# FPGA.net
KiCad netlist of a schematic drawn in Altium Designer
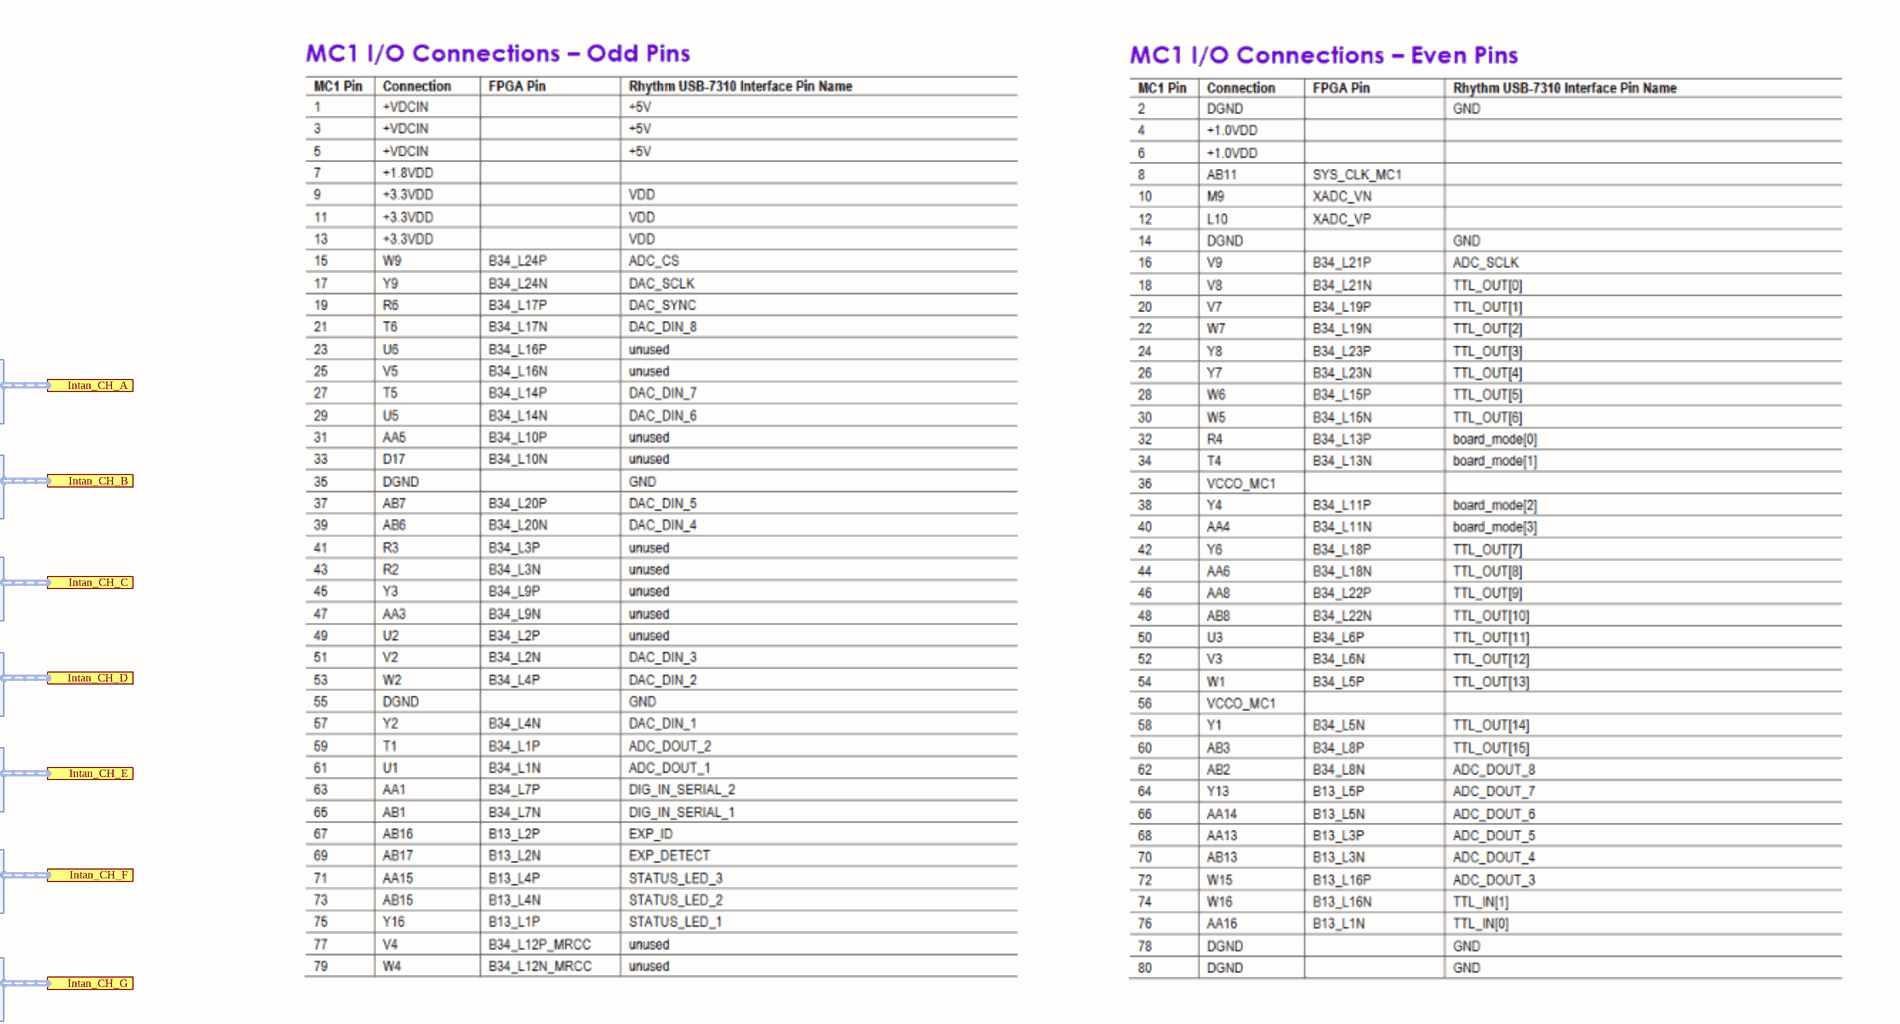
[diagram p0: FPGA.SchDoc, top right]
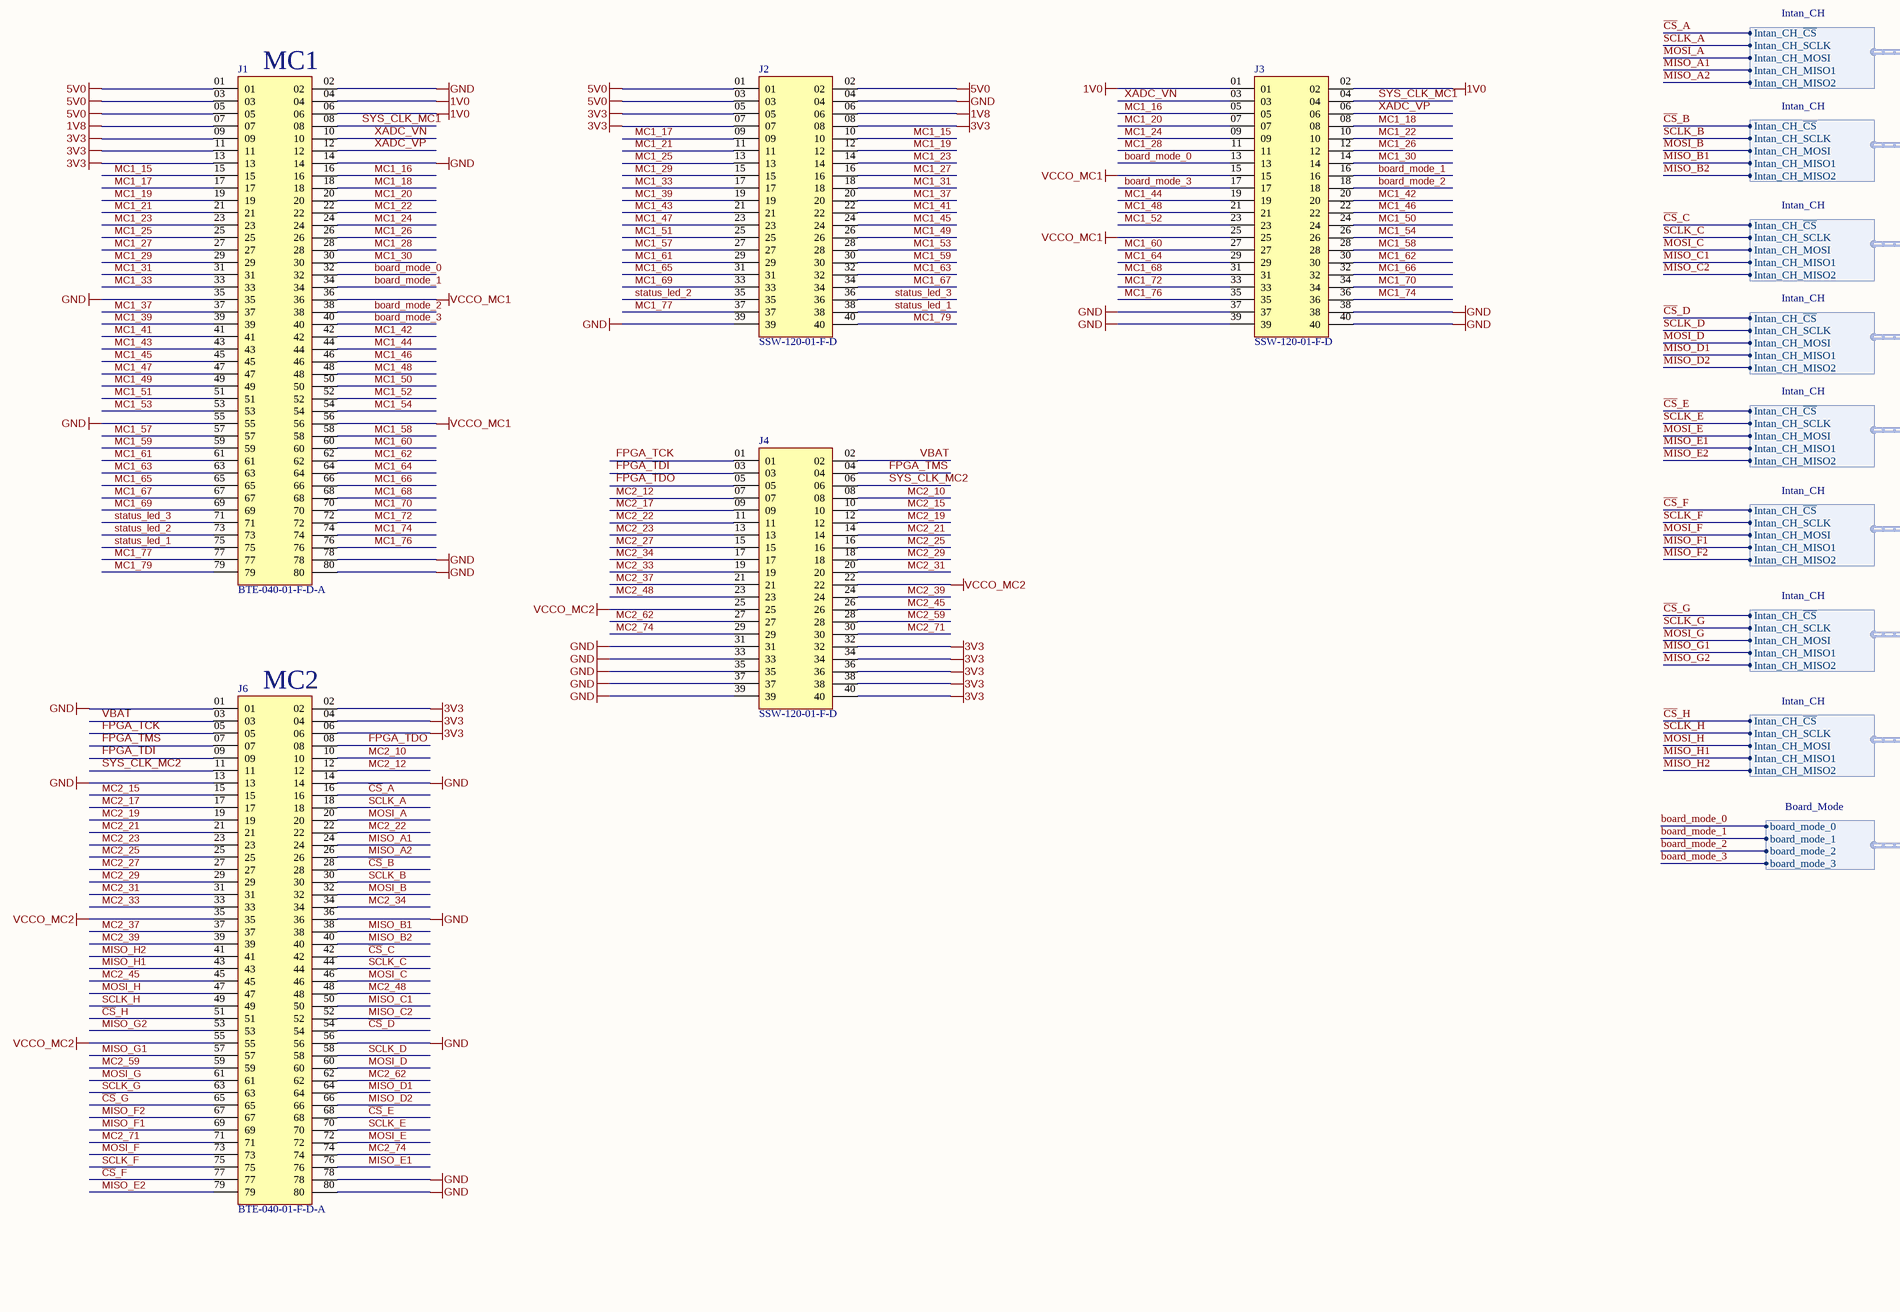
[diagram p1: FPGA.SchDoc, bottom left]
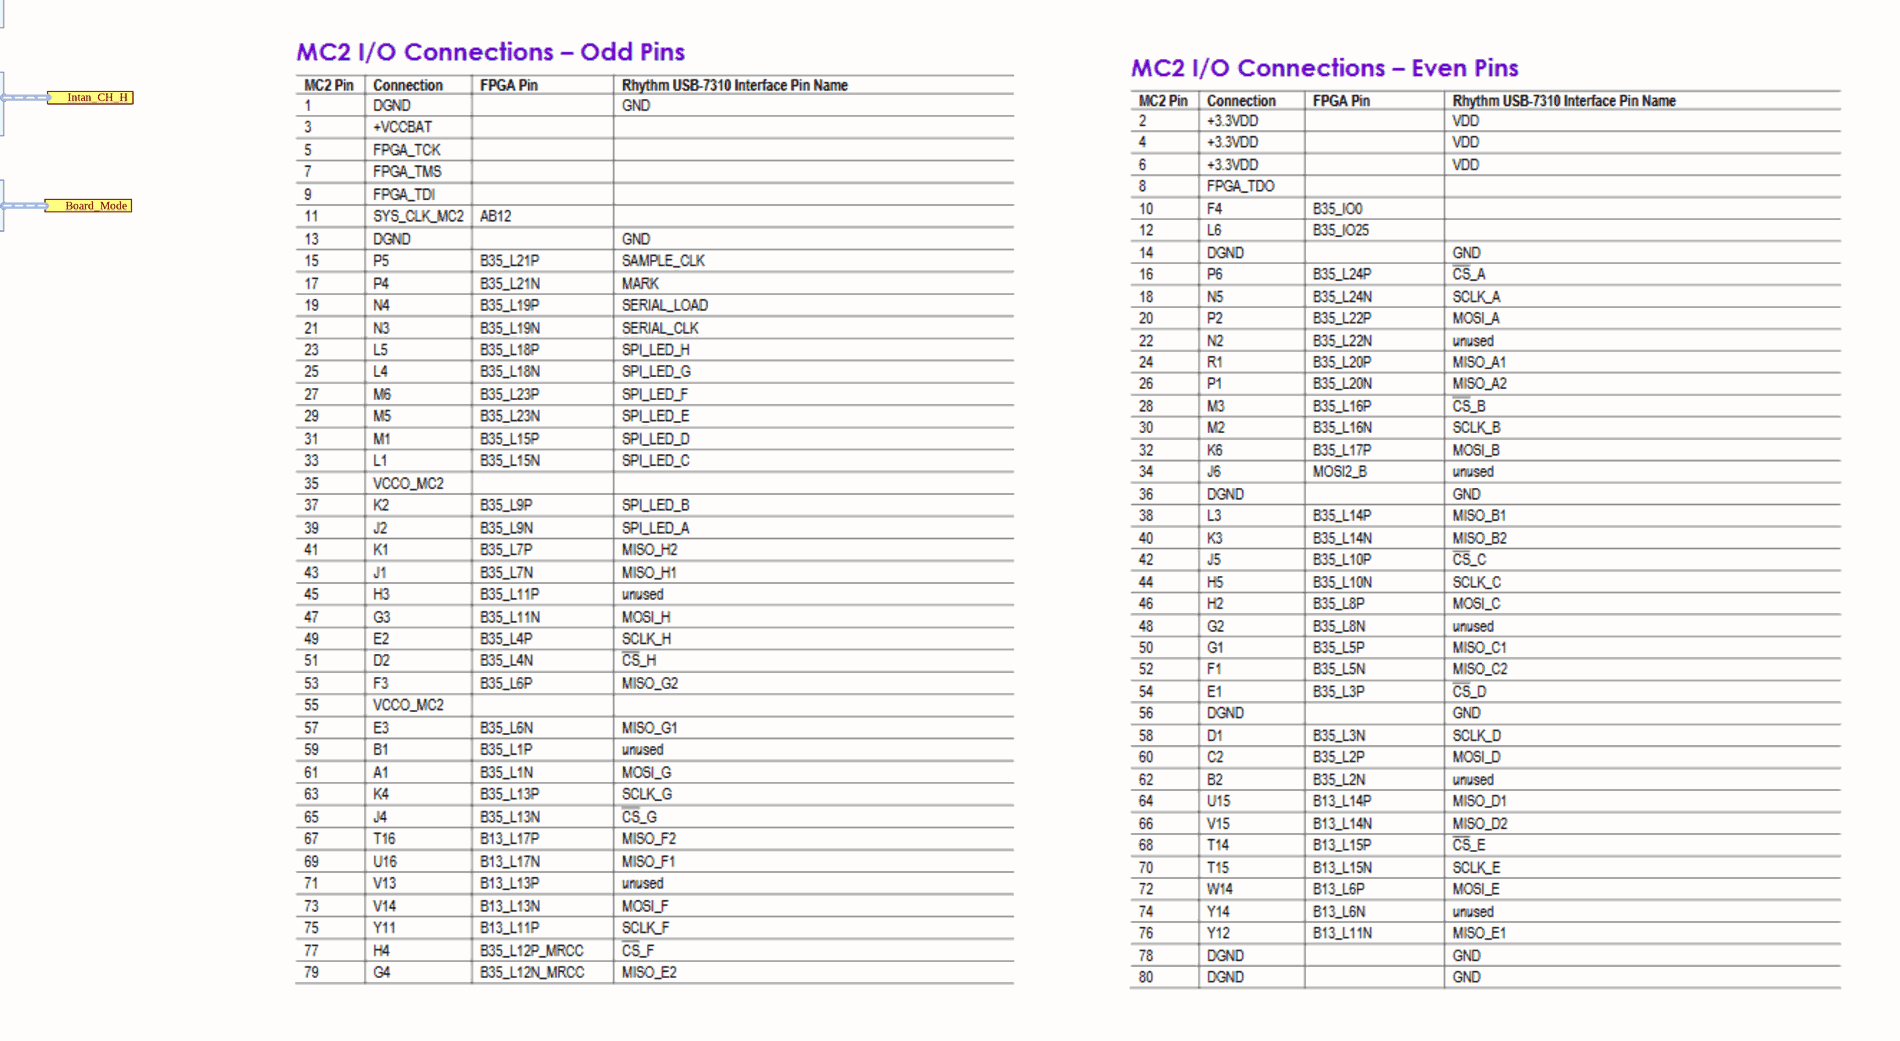
[diagram p2: FPGA.SchDoc, bottom right]

(export (version "E")
  (design (tool "Eeschema 10.0.6"))
  (components
    (comp (ref "J1")
      (value "BTE-040-01-F-D-A")
      (footprint "SAMTEC_BTE-040-01-F-D-A")
      (description "80 Position Connector Header, Outer Shroud Contacts Surface Mount Gold")
      (fields (field (name "MF") "Samtec"))
      (libsource (lib "UHDEMG") (part "CON_FPGA_SMD"))
    )
    (comp (ref "J2")
      (value "SSW-120-01-F-D")
      (footprint "SAMTEC_SSW-120-01-F-D")
      (description "40 Position Receptacle Connector 0.100\" (2.54mm) Through Hole Gold")
      (fields (field (name "MF") "Samtec"))
      (libsource (lib "UHDEMG") (part "CON_HEADF_2X20"))
    )
    (comp (ref "J3")
      (value "SSW-120-01-F-D")
      (footprint "SAMTEC_SSW-120-01-F-D")
      (description "40 Position Receptacle Connector 0.100\" (2.54mm) Through Hole Gold")
      (fields (field (name "MF") "Samtec"))
      (libsource (lib "UHDEMG") (part "CON_HEADF_2X20"))
    )
    (comp (ref "J4")
      (value "SSW-120-01-F-D")
      (footprint "SAMTEC_SSW-120-01-F-D")
      (description "40 Position Receptacle Connector 0.100\" (2.54mm) Through Hole Gold")
      (fields (field (name "MF") "Samtec"))
      (libsource (lib "UHDEMG") (part "CON_HEADF_2X20"))
    )
    (comp (ref "J6")
      (value "BTE-040-01-F-D-A")
      (footprint "SAMTEC_BTE-040-01-F-D-A")
      (description "80 Position Connector Header, Outer Shroud Contacts Surface Mount Gold")
      (fields (field (name "MF") "Samtec"))
      (libsource (lib "UHDEMG") (part "CON_FPGA_SMD"))
    )
  )
  (nets
    (net (code "3") (name "/FPGA_TCK") (class "Default")
      (node (ref "J4") (pin "01") (pinfunction "01_01") (pintype "passive"))
      (node (ref "J6") (pin "05") (pinfunction "05_05") (pintype "passive"))
    )
    (net (code "4") (name "/FPGA_TDI") (class "Default")
      (node (ref "J4") (pin "03") (pinfunction "03_03") (pintype "passive"))
      (node (ref "J6") (pin "09") (pinfunction "09_09") (pintype "passive"))
    )
    (net (code "5") (name "/FPGA_TDO") (class "Default")
      (node (ref "J4") (pin "05") (pinfunction "05_05") (pintype "passive"))
      (node (ref "J6") (pin "08") (pinfunction "08_08") (pintype "passive"))
    )
    (net (code "6") (name "/FPGA_TMS") (class "Default")
      (node (ref "J4") (pin "04") (pinfunction "04_04") (pintype "passive"))
      (node (ref "J6") (pin "07") (pinfunction "07_07") (pintype "passive"))
    )
    (net (code "7") (name "/MC1_15") (class "Default")
      (node (ref "J1") (pin "15") (pinfunction "15_15") (pintype "passive"))
      (node (ref "J2") (pin "10") (pinfunction "10_10") (pintype "passive"))
    )
    (net (code "8") (name "/MC1_16") (class "Default")
      (node (ref "J1") (pin "16") (pinfunction "16_16") (pintype "passive"))
      (node (ref "J3") (pin "05") (pinfunction "05_05") (pintype "passive"))
    )
    (net (code "9") (name "/MC1_17") (class "Default")
      (node (ref "J1") (pin "17") (pinfunction "17_17") (pintype "passive"))
      (node (ref "J2") (pin "09") (pinfunction "09_09") (pintype "passive"))
    )
    (net (code "10") (name "/MC1_18") (class "Default")
      (node (ref "J1") (pin "18") (pinfunction "18_18") (pintype "passive"))
      (node (ref "J3") (pin "08") (pinfunction "08_08") (pintype "passive"))
    )
    (net (code "11") (name "/MC1_19") (class "Default")
      (node (ref "J1") (pin "19") (pinfunction "19_19") (pintype "passive"))
      (node (ref "J2") (pin "12") (pinfunction "12_12") (pintype "passive"))
    )
    (net (code "12") (name "/MC1_20") (class "Default")
      (node (ref "J1") (pin "20") (pinfunction "20_20") (pintype "passive"))
      (node (ref "J3") (pin "07") (pinfunction "07_07") (pintype "passive"))
    )
    (net (code "13") (name "/MC1_21") (class "Default")
      (node (ref "J1") (pin "21") (pinfunction "21_21") (pintype "passive"))
      (node (ref "J2") (pin "11") (pinfunction "11_11") (pintype "passive"))
    )
    (net (code "14") (name "/MC1_22") (class "Default")
      (node (ref "J1") (pin "22") (pinfunction "22_22") (pintype "passive"))
      (node (ref "J3") (pin "10") (pinfunction "10_10") (pintype "passive"))
    )
    (net (code "15") (name "/MC1_23") (class "Default")
      (node (ref "J1") (pin "23") (pinfunction "23_23") (pintype "passive"))
      (node (ref "J2") (pin "14") (pinfunction "14_14") (pintype "passive"))
    )
    (net (code "16") (name "/MC1_24") (class "Default")
      (node (ref "J1") (pin "24") (pinfunction "24_24") (pintype "passive"))
      (node (ref "J3") (pin "09") (pinfunction "09_09") (pintype "passive"))
    )
    (net (code "17") (name "/MC1_25") (class "Default")
      (node (ref "J1") (pin "25") (pinfunction "25_25") (pintype "passive"))
      (node (ref "J2") (pin "13") (pinfunction "13_13") (pintype "passive"))
    )
    (net (code "18") (name "/MC1_26") (class "Default")
      (node (ref "J1") (pin "26") (pinfunction "26_26") (pintype "passive"))
      (node (ref "J3") (pin "12") (pinfunction "12_12") (pintype "passive"))
    )
    (net (code "19") (name "/MC1_27") (class "Default")
      (node (ref "J1") (pin "27") (pinfunction "27_27") (pintype "passive"))
      (node (ref "J2") (pin "16") (pinfunction "16_16") (pintype "passive"))
    )
    (net (code "20") (name "/MC1_28") (class "Default")
      (node (ref "J1") (pin "28") (pinfunction "28_28") (pintype "passive"))
      (node (ref "J3") (pin "11") (pinfunction "11_11") (pintype "passive"))
    )
    (net (code "21") (name "/MC1_29") (class "Default")
      (node (ref "J1") (pin "29") (pinfunction "29_29") (pintype "passive"))
      (node (ref "J2") (pin "15") (pinfunction "15_15") (pintype "passive"))
    )
    (net (code "22") (name "/MC1_30") (class "Default")
      (node (ref "J1") (pin "30") (pinfunction "30_30") (pintype "passive"))
      (node (ref "J3") (pin "14") (pinfunction "14_14") (pintype "passive"))
    )
    (net (code "23") (name "/MC1_31") (class "Default")
      (node (ref "J1") (pin "31") (pinfunction "31_31") (pintype "passive"))
      (node (ref "J2") (pin "18") (pinfunction "18_18") (pintype "passive"))
    )
    (net (code "24") (name "/MC1_33") (class "Default")
      (node (ref "J1") (pin "33") (pinfunction "33_33") (pintype "passive"))
      (node (ref "J2") (pin "17") (pinfunction "17_17") (pintype "passive"))
    )
    (net (code "25") (name "/MC1_37") (class "Default")
      (node (ref "J1") (pin "37") (pinfunction "37_37") (pintype "passive"))
      (node (ref "J2") (pin "20") (pinfunction "20_20") (pintype "passive"))
    )
    (net (code "26") (name "/MC1_39") (class "Default")
      (node (ref "J1") (pin "39") (pinfunction "39_39") (pintype "passive"))
      (node (ref "J2") (pin "19") (pinfunction "19_19") (pintype "passive"))
    )
    (net (code "27") (name "/MC1_41") (class "Default")
      (node (ref "J1") (pin "41") (pinfunction "41_41") (pintype "passive"))
      (node (ref "J2") (pin "22") (pinfunction "22_22") (pintype "passive"))
    )
    (net (code "28") (name "/MC1_42") (class "Default")
      (node (ref "J1") (pin "42") (pinfunction "42_42") (pintype "passive"))
      (node (ref "J3") (pin "20") (pinfunction "20_20") (pintype "passive"))
    )
    (net (code "29") (name "/MC1_43") (class "Default")
      (node (ref "J1") (pin "43") (pinfunction "43_43") (pintype "passive"))
      (node (ref "J2") (pin "21") (pinfunction "21_21") (pintype "passive"))
    )
    (net (code "30") (name "/MC1_44") (class "Default")
      (node (ref "J1") (pin "44") (pinfunction "44_44") (pintype "passive"))
      (node (ref "J3") (pin "19") (pinfunction "19_19") (pintype "passive"))
    )
    (net (code "31") (name "/MC1_45") (class "Default")
      (node (ref "J1") (pin "45") (pinfunction "45_45") (pintype "passive"))
      (node (ref "J2") (pin "24") (pinfunction "24_24") (pintype "passive"))
    )
    (net (code "32") (name "/MC1_46") (class "Default")
      (node (ref "J1") (pin "46") (pinfunction "46_46") (pintype "passive"))
      (node (ref "J3") (pin "22") (pinfunction "22_22") (pintype "passive"))
    )
    (net (code "33") (name "/MC1_47") (class "Default")
      (node (ref "J1") (pin "47") (pinfunction "47_47") (pintype "passive"))
      (node (ref "J2") (pin "23") (pinfunction "23_23") (pintype "passive"))
    )
    (net (code "34") (name "/MC1_48") (class "Default")
      (node (ref "J1") (pin "48") (pinfunction "48_48") (pintype "passive"))
      (node (ref "J3") (pin "21") (pinfunction "21_21") (pintype "passive"))
    )
    (net (code "35") (name "/MC1_49") (class "Default")
      (node (ref "J1") (pin "49") (pinfunction "49_49") (pintype "passive"))
      (node (ref "J2") (pin "26") (pinfunction "26_26") (pintype "passive"))
    )
    (net (code "36") (name "/MC1_50") (class "Default")
      (node (ref "J1") (pin "50") (pinfunction "50_50") (pintype "passive"))
      (node (ref "J3") (pin "24") (pinfunction "24_24") (pintype "passive"))
    )
    (net (code "37") (name "/MC1_51") (class "Default")
      (node (ref "J1") (pin "51") (pinfunction "51_51") (pintype "passive"))
      (node (ref "J2") (pin "25") (pinfunction "25_25") (pintype "passive"))
    )
    (net (code "38") (name "/MC1_52") (class "Default")
      (node (ref "J1") (pin "52") (pinfunction "52_52") (pintype "passive"))
      (node (ref "J3") (pin "23") (pinfunction "23_23") (pintype "passive"))
    )
    (net (code "39") (name "/MC1_53") (class "Default")
      (node (ref "J1") (pin "53") (pinfunction "53_53") (pintype "passive"))
      (node (ref "J2") (pin "28") (pinfunction "28_28") (pintype "passive"))
    )
    (net (code "40") (name "/MC1_54") (class "Default")
      (node (ref "J1") (pin "54") (pinfunction "54_54") (pintype "passive"))
      (node (ref "J3") (pin "26") (pinfunction "26_26") (pintype "passive"))
    )
    (net (code "41") (name "/MC1_57") (class "Default")
      (node (ref "J1") (pin "57") (pinfunction "57_57") (pintype "passive"))
      (node (ref "J2") (pin "27") (pinfunction "27_27") (pintype "passive"))
    )
    (net (code "42") (name "/MC1_58") (class "Default")
      (node (ref "J1") (pin "58") (pinfunction "58_58") (pintype "passive"))
      (node (ref "J3") (pin "28") (pinfunction "28_28") (pintype "passive"))
    )
    (net (code "43") (name "/MC1_59") (class "Default")
      (node (ref "J1") (pin "59") (pinfunction "59_59") (pintype "passive"))
      (node (ref "J2") (pin "30") (pinfunction "30_30") (pintype "passive"))
    )
    (net (code "44") (name "/MC1_60") (class "Default")
      (node (ref "J1") (pin "60") (pinfunction "60_60") (pintype "passive"))
      (node (ref "J3") (pin "27") (pinfunction "27_27") (pintype "passive"))
    )
    (net (code "45") (name "/MC1_61") (class "Default")
      (node (ref "J1") (pin "61") (pinfunction "61_61") (pintype "passive"))
      (node (ref "J2") (pin "29") (pinfunction "29_29") (pintype "passive"))
    )
    (net (code "46") (name "/MC1_62") (class "Default")
      (node (ref "J1") (pin "62") (pinfunction "62_62") (pintype "passive"))
      (node (ref "J3") (pin "30") (pinfunction "30_30") (pintype "passive"))
    )
    (net (code "47") (name "/MC1_63") (class "Default")
      (node (ref "J1") (pin "63") (pinfunction "63_63") (pintype "passive"))
      (node (ref "J2") (pin "32") (pinfunction "32_32") (pintype "passive"))
    )
    (net (code "48") (name "/MC1_64") (class "Default")
      (node (ref "J1") (pin "64") (pinfunction "64_64") (pintype "passive"))
      (node (ref "J3") (pin "29") (pinfunction "29_29") (pintype "passive"))
    )
    (net (code "49") (name "/MC1_65") (class "Default")
      (node (ref "J1") (pin "65") (pinfunction "65_65") (pintype "passive"))
      (node (ref "J2") (pin "31") (pinfunction "31_31") (pintype "passive"))
    )
    (net (code "50") (name "/MC1_66") (class "Default")
      (node (ref "J1") (pin "66") (pinfunction "66_66") (pintype "passive"))
      (node (ref "J3") (pin "32") (pinfunction "32_32") (pintype "passive"))
    )
    (net (code "51") (name "/MC1_67") (class "Default")
      (node (ref "J1") (pin "67") (pinfunction "67_67") (pintype "passive"))
      (node (ref "J2") (pin "34") (pinfunction "34_34") (pintype "passive"))
    )
    (net (code "52") (name "/MC1_68") (class "Default")
      (node (ref "J1") (pin "68") (pinfunction "68_68") (pintype "passive"))
      (node (ref "J3") (pin "31") (pinfunction "31_31") (pintype "passive"))
    )
    (net (code "53") (name "/MC1_69") (class "Default")
      (node (ref "J1") (pin "69") (pinfunction "69_69") (pintype "passive"))
      (node (ref "J2") (pin "33") (pinfunction "33_33") (pintype "passive"))
    )
    (net (code "54") (name "/MC1_70") (class "Default")
      (node (ref "J1") (pin "70") (pinfunction "70_70") (pintype "passive"))
      (node (ref "J3") (pin "34") (pinfunction "34_34") (pintype "passive"))
    )
    (net (code "55") (name "/MC1_72") (class "Default")
      (node (ref "J1") (pin "72") (pinfunction "72_72") (pintype "passive"))
      (node (ref "J3") (pin "33") (pinfunction "33_33") (pintype "passive"))
    )
    (net (code "56") (name "/MC1_74") (class "Default")
      (node (ref "J1") (pin "74") (pinfunction "74_74") (pintype "passive"))
      (node (ref "J3") (pin "36") (pinfunction "36_36") (pintype "passive"))
    )
    (net (code "57") (name "/MC1_76") (class "Default")
      (node (ref "J1") (pin "76") (pinfunction "76_76") (pintype "passive"))
      (node (ref "J3") (pin "35") (pinfunction "35_35") (pintype "passive"))
    )
    (net (code "58") (name "/MC1_77") (class "Default")
      (node (ref "J1") (pin "77") (pinfunction "77_77") (pintype "passive"))
      (node (ref "J2") (pin "37") (pinfunction "37_37") (pintype "passive"))
    )
    (net (code "59") (name "/MC1_79") (class "Default")
      (node (ref "J1") (pin "79") (pinfunction "79_79") (pintype "passive"))
      (node (ref "J2") (pin "40") (pinfunction "40_40") (pintype "passive"))
    )
    (net (code "60") (name "/MC2_10") (class "Default")
      (node (ref "J4") (pin "08") (pinfunction "08_08") (pintype "passive"))
      (node (ref "J6") (pin "10") (pinfunction "10_10") (pintype "passive"))
    )
    (net (code "61") (name "/MC2_12") (class "Default")
      (node (ref "J4") (pin "07") (pinfunction "07_07") (pintype "passive"))
      (node (ref "J6") (pin "12") (pinfunction "12_12") (pintype "passive"))
    )
    (net (code "62") (name "/MC2_15") (class "Default")
      (node (ref "J4") (pin "10") (pinfunction "10_10") (pintype "passive"))
      (node (ref "J6") (pin "15") (pinfunction "15_15") (pintype "passive"))
    )
    (net (code "63") (name "/MC2_17") (class "Default")
      (node (ref "J4") (pin "09") (pinfunction "09_09") (pintype "passive"))
      (node (ref "J6") (pin "17") (pinfunction "17_17") (pintype "passive"))
    )
    (net (code "64") (name "/MC2_19") (class "Default")
      (node (ref "J4") (pin "12") (pinfunction "12_12") (pintype "passive"))
      (node (ref "J6") (pin "19") (pinfunction "19_19") (pintype "passive"))
    )
    (net (code "65") (name "/MC2_21") (class "Default")
      (node (ref "J4") (pin "14") (pinfunction "14_14") (pintype "passive"))
      (node (ref "J6") (pin "21") (pinfunction "21_21") (pintype "passive"))
    )
    (net (code "66") (name "/MC2_22") (class "Default")
      (node (ref "J4") (pin "11") (pinfunction "11_11") (pintype "passive"))
      (node (ref "J6") (pin "22") (pinfunction "22_22") (pintype "passive"))
    )
    (net (code "67") (name "/MC2_23") (class "Default")
      (node (ref "J4") (pin "13") (pinfunction "13_13") (pintype "passive"))
      (node (ref "J6") (pin "23") (pinfunction "23_23") (pintype "passive"))
    )
    (net (code "68") (name "/MC2_25") (class "Default")
      (node (ref "J4") (pin "16") (pinfunction "16_16") (pintype "passive"))
      (node (ref "J6") (pin "25") (pinfunction "25_25") (pintype "passive"))
    )
    (net (code "69") (name "/MC2_27") (class "Default")
      (node (ref "J4") (pin "15") (pinfunction "15_15") (pintype "passive"))
      (node (ref "J6") (pin "27") (pinfunction "27_27") (pintype "passive"))
    )
    (net (code "70") (name "/MC2_29") (class "Default")
      (node (ref "J4") (pin "18") (pinfunction "18_18") (pintype "passive"))
      (node (ref "J6") (pin "29") (pinfunction "29_29") (pintype "passive"))
    )
    (net (code "71") (name "/MC2_31") (class "Default")
      (node (ref "J4") (pin "20") (pinfunction "20_20") (pintype "passive"))
      (node (ref "J6") (pin "31") (pinfunction "31_31") (pintype "passive"))
    )
    (net (code "72") (name "/MC2_33") (class "Default")
      (node (ref "J4") (pin "19") (pinfunction "19_19") (pintype "passive"))
      (node (ref "J6") (pin "33") (pinfunction "33_33") (pintype "passive"))
    )
    (net (code "73") (name "/MC2_34") (class "Default")
      (node (ref "J4") (pin "17") (pinfunction "17_17") (pintype "passive"))
      (node (ref "J6") (pin "34") (pinfunction "34_34") (pintype "passive"))
    )
    (net (code "74") (name "/MC2_37") (class "Default")
      (node (ref "J4") (pin "21") (pinfunction "21_21") (pintype "passive"))
      (node (ref "J6") (pin "37") (pinfunction "37_37") (pintype "passive"))
    )
    (net (code "75") (name "/MC2_39") (class "Default")
      (node (ref "J4") (pin "24") (pinfunction "24_24") (pintype "passive"))
      (node (ref "J6") (pin "39") (pinfunction "39_39") (pintype "passive"))
    )
    (net (code "76") (name "/MC2_45") (class "Default")
      (node (ref "J4") (pin "26") (pinfunction "26_26") (pintype "passive"))
      (node (ref "J6") (pin "45") (pinfunction "45_45") (pintype "passive"))
    )
    (net (code "77") (name "/MC2_48") (class "Default")
      (node (ref "J4") (pin "23") (pinfunction "23_23") (pintype "passive"))
      (node (ref "J6") (pin "48") (pinfunction "48_48") (pintype "passive"))
    )
    (net (code "78") (name "/MC2_59") (class "Default")
      (node (ref "J4") (pin "28") (pinfunction "28_28") (pintype "passive"))
      (node (ref "J6") (pin "59") (pinfunction "59_59") (pintype "passive"))
    )
    (net (code "79") (name "/MC2_62") (class "Default")
      (node (ref "J4") (pin "27") (pinfunction "27_27") (pintype "passive"))
      (node (ref "J6") (pin "62") (pinfunction "62_62") (pintype "passive"))
    )
    (net (code "80") (name "/MC2_71") (class "Default")
      (node (ref "J4") (pin "30") (pinfunction "30_30") (pintype "passive"))
      (node (ref "J6") (pin "71") (pinfunction "71_71") (pintype "passive"))
    )
    (net (code "81") (name "/MC2_74") (class "Default")
      (node (ref "J4") (pin "29") (pinfunction "29_29") (pintype "passive"))
      (node (ref "J6") (pin "74") (pinfunction "74_74") (pintype "passive"))
    )
    (net (code "82") (name "/MISO_A1") (class "Default")
      (node (ref "J6") (pin "24") (pinfunction "24_24") (pintype "passive"))
    )
    (net (code "83") (name "/MISO_A2") (class "Default")
      (node (ref "J6") (pin "26") (pinfunction "26_26") (pintype "passive"))
    )
    (net (code "84") (name "/MISO_B1") (class "Default")
      (node (ref "J6") (pin "38") (pinfunction "38_38") (pintype "passive"))
    )
    (net (code "85") (name "/MISO_B2") (class "Default")
      (node (ref "J6") (pin "40") (pinfunction "40_40") (pintype "passive"))
    )
    (net (code "86") (name "/MISO_C1") (class "Default")
      (node (ref "J6") (pin "50") (pinfunction "50_50") (pintype "passive"))
    )
    (net (code "87") (name "/MISO_C2") (class "Default")
      (node (ref "J6") (pin "52") (pinfunction "52_52") (pintype "passive"))
    )
    (net (code "88") (name "/MISO_D1") (class "Default")
      (node (ref "J6") (pin "64") (pinfunction "64_64") (pintype "passive"))
    )
    (net (code "89") (name "/MISO_D2") (class "Default")
      (node (ref "J6") (pin "66") (pinfunction "66_66") (pintype "passive"))
    )
    (net (code "90") (name "/MISO_E1") (class "Default")
      (node (ref "J6") (pin "76") (pinfunction "76_76") (pintype "passive"))
    )
    (net (code "91") (name "/MISO_E2") (class "Default")
      (node (ref "J6") (pin "79") (pinfunction "79_79") (pintype "passive"))
    )
    (net (code "92") (name "/MISO_F1") (class "Default")
      (node (ref "J6") (pin "69") (pinfunction "69_69") (pintype "passive"))
    )
    (net (code "93") (name "/MISO_F2") (class "Default")
      (node (ref "J6") (pin "67") (pinfunction "67_67") (pintype "passive"))
    )
    (net (code "94") (name "/MISO_G1") (class "Default")
      (node (ref "J6") (pin "57") (pinfunction "57_57") (pintype "passive"))
    )
    (net (code "95") (name "/MISO_G2") (class "Default")
      (node (ref "J6") (pin "53") (pinfunction "53_53") (pintype "passive"))
    )
    (net (code "96") (name "/MISO_H1") (class "Default")
      (node (ref "J6") (pin "43") (pinfunction "43_43") (pintype "passive"))
    )
    (net (code "97") (name "/MISO_H2") (class "Default")
      (node (ref "J6") (pin "41") (pinfunction "41_41") (pintype "passive"))
    )
    (net (code "98") (name "/MOSI_A") (class "Default")
      (node (ref "J6") (pin "20") (pinfunction "20_20") (pintype "passive"))
    )
    (net (code "99") (name "/MOSI_B") (class "Default")
      (node (ref "J6") (pin "32") (pinfunction "32_32") (pintype "passive"))
    )
    (net (code "100") (name "/MOSI_C") (class "Default")
      (node (ref "J6") (pin "46") (pinfunction "46_46") (pintype "passive"))
    )
    (net (code "101") (name "/MOSI_D") (class "Default")
      (node (ref "J6") (pin "60") (pinfunction "60_60") (pintype "passive"))
    )
    (net (code "102") (name "/MOSI_E") (class "Default")
      (node (ref "J6") (pin "72") (pinfunction "72_72") (pintype "passive"))
    )
    (net (code "103") (name "/MOSI_F") (class "Default")
      (node (ref "J6") (pin "73") (pinfunction "73_73") (pintype "passive"))
    )
    (net (code "104") (name "/MOSI_G") (class "Default")
      (node (ref "J6") (pin "61") (pinfunction "61_61") (pintype "passive"))
    )
    (net (code "105") (name "/MOSI_H") (class "Default")
      (node (ref "J6") (pin "47") (pinfunction "47_47") (pintype "passive"))
    )
    (net (code "106") (name "/SCLK_A") (class "Default")
      (node (ref "J6") (pin "18") (pinfunction "18_18") (pintype "passive"))
    )
    (net (code "107") (name "/SCLK_B") (class "Default")
      (node (ref "J6") (pin "30") (pinfunction "30_30") (pintype "passive"))
    )
    (net (code "108") (name "/SCLK_C") (class "Default")
      (node (ref "J6") (pin "44") (pinfunction "44_44") (pintype "passive"))
    )
    (net (code "109") (name "/SCLK_D") (class "Default")
      (node (ref "J6") (pin "58") (pinfunction "58_58") (pintype "passive"))
    )
    (net (code "110") (name "/SCLK_E") (class "Default")
      (node (ref "J6") (pin "70") (pinfunction "70_70") (pintype "passive"))
    )
    (net (code "111") (name "/SCLK_F") (class "Default")
      (node (ref "J6") (pin "75") (pinfunction "75_75") (pintype "passive"))
    )
    (net (code "112") (name "/SCLK_G") (class "Default")
      (node (ref "J6") (pin "63") (pinfunction "63_63") (pintype "passive"))
    )
    (net (code "113") (name "/SCLK_H") (class "Default")
      (node (ref "J6") (pin "49") (pinfunction "49_49") (pintype "passive"))
    )
    (net (code "114") (name "/SYS_CLK_MC1") (class "Default")
      (node (ref "J1") (pin "08") (pinfunction "08_08") (pintype "passive"))
      (node (ref "J3") (pin "04") (pinfunction "04_04") (pintype "passive"))
    )
    (net (code "115") (name "/SYS_CLK_MC2") (class "Default")
      (node (ref "J4") (pin "06") (pinfunction "06_06") (pintype "passive"))
      (node (ref "J6") (pin "11") (pinfunction "11_11") (pintype "passive"))
    )
    (net (code "116") (name "/VBAT") (class "Default")
      (node (ref "J4") (pin "02") (pinfunction "02_02") (pintype "passive"))
      (node (ref "J6") (pin "03") (pinfunction "03_03") (pintype "passive"))
    )
    (net (code "117") (name "/XADC_VN") (class "Default")
      (node (ref "J1") (pin "10") (pinfunction "10_10") (pintype "passive"))
      (node (ref "J3") (pin "03") (pinfunction "03_03") (pintype "passive"))
    )
    (net (code "118") (name "/XADC_VP") (class "Default")
      (node (ref "J1") (pin "12") (pinfunction "12_12") (pintype "passive"))
      (node (ref "J3") (pin "06") (pinfunction "06_06") (pintype "passive"))
    )
    (net (code "119") (name "/board_mode_0") (class "Default")
      (node (ref "J1") (pin "32") (pinfunction "32_32") (pintype "passive"))
      (node (ref "J3") (pin "13") (pinfunction "13_13") (pintype "passive"))
    )
    (net (code "120") (name "/board_mode_1") (class "Default")
      (node (ref "J1") (pin "34") (pinfunction "34_34") (pintype "passive"))
      (node (ref "J3") (pin "16") (pinfunction "16_16") (pintype "passive"))
    )
    (net (code "121") (name "/board_mode_2") (class "Default")
      (node (ref "J1") (pin "38") (pinfunction "38_38") (pintype "passive"))
      (node (ref "J3") (pin "18") (pinfunction "18_18") (pintype "passive"))
    )
    (net (code "122") (name "/board_mode_3") (class "Default")
      (node (ref "J1") (pin "40") (pinfunction "40_40") (pintype "passive"))
      (node (ref "J3") (pin "17") (pinfunction "17_17") (pintype "passive"))
    )
    (net (code "123") (name "/status_led_1") (class "Default")
      (node (ref "J1") (pin "75") (pinfunction "75_75") (pintype "passive"))
      (node (ref "J2") (pin "38") (pinfunction "38_38") (pintype "passive"))
    )
    (net (code "124") (name "/status_led_2") (class "Default")
      (node (ref "J1") (pin "73") (pinfunction "73_73") (pintype "passive"))
      (node (ref "J2") (pin "35") (pinfunction "35_35") (pintype "passive"))
    )
    (net (code "125") (name "/status_led_3") (class "Default")
      (node (ref "J1") (pin "71") (pinfunction "71_71") (pintype "passive"))
      (node (ref "J2") (pin "36") (pinfunction "36_36") (pintype "passive"))
    )
    (net (code "128") (name "/~{CS}_A") (class "Default")
      (node (ref "J6") (pin "16") (pinfunction "16_16") (pintype "passive"))
    )
    (net (code "129") (name "/~{CS}_B") (class "Default")
      (node (ref "J6") (pin "28") (pinfunction "28_28") (pintype "passive"))
    )
    (net (code "130") (name "/~{CS}_C") (class "Default")
      (node (ref "J6") (pin "42") (pinfunction "42_42") (pintype "passive"))
    )
    (net (code "131") (name "/~{CS}_D") (class "Default")
      (node (ref "J6") (pin "54") (pinfunction "54_54") (pintype "passive"))
    )
    (net (code "132") (name "/~{CS}_E") (class "Default")
      (node (ref "J6") (pin "68") (pinfunction "68_68") (pintype "passive"))
    )
    (net (code "133") (name "/~{CS}_F") (class "Default")
      (node (ref "J6") (pin "77") (pinfunction "77_77") (pintype "passive"))
    )
    (net (code "134") (name "/~{CS}_G") (class "Default")
      (node (ref "J6") (pin "65") (pinfunction "65_65") (pintype "passive"))
    )
    (net (code "135") (name "/~{CS}_H") (class "Default")
      (node (ref "J6") (pin "51") (pinfunction "51_51") (pintype "passive"))
    )
    (net (code "136") (name "1V0") (class "Default")
      (node (ref "J1") (pin "04") (pinfunction "04_04") (pintype "passive"))
      (node (ref "J1") (pin "06") (pinfunction "06_06") (pintype "passive"))
      (node (ref "J3") (pin "01") (pinfunction "01_01") (pintype "passive"))
      (node (ref "J3") (pin "02") (pinfunction "02_02") (pintype "passive"))
    )
    (net (code "137") (name "1V8") (class "Default")
      (node (ref "J1") (pin "07") (pinfunction "07_07") (pintype "passive"))
      (node (ref "J2") (pin "06") (pinfunction "06_06") (pintype "passive"))
    )
    (net (code "138") (name "3V3") (class "Default")
      (node (ref "J1") (pin "09") (pinfunction "09_09") (pintype "passive"))
      (node (ref "J1") (pin "11") (pinfunction "11_11") (pintype "passive"))
      (node (ref "J1") (pin "13") (pinfunction "13_13") (pintype "passive"))
      (node (ref "J2") (pin "05") (pinfunction "05_05") (pintype "passive"))
      (node (ref "J2") (pin "07") (pinfunction "07_07") (pintype "passive"))
      (node (ref "J2") (pin "08") (pinfunction "08_08") (pintype "passive"))
      (node (ref "J4") (pin "32") (pinfunction "32_32") (pintype "passive"))
      (node (ref "J4") (pin "34") (pinfunction "34_34") (pintype "passive"))
      (node (ref "J4") (pin "36") (pinfunction "36_36") (pintype "passive"))
      (node (ref "J4") (pin "38") (pinfunction "38_38") (pintype "passive"))
      (node (ref "J4") (pin "40") (pinfunction "40_40") (pintype "passive"))
      (node (ref "J6") (pin "02") (pinfunction "02_02") (pintype "passive"))
      (node (ref "J6") (pin "04") (pinfunction "04_04") (pintype "passive"))
      (node (ref "J6") (pin "06") (pinfunction "06_06") (pintype "passive"))
    )
    (net (code "139") (name "5V0") (class "Default")
      (node (ref "J1") (pin "01") (pinfunction "01_01") (pintype "passive"))
      (node (ref "J1") (pin "03") (pinfunction "03_03") (pintype "passive"))
      (node (ref "J1") (pin "05") (pinfunction "05_05") (pintype "passive"))
      (node (ref "J2") (pin "01") (pinfunction "01_01") (pintype "passive"))
      (node (ref "J2") (pin "02") (pinfunction "02_02") (pintype "passive"))
      (node (ref "J2") (pin "03") (pinfunction "03_03") (pintype "passive"))
    )
    (net (code "140") (name "GND") (class "Default")
      (node (ref "J1") (pin "02") (pinfunction "02_02") (pintype "passive"))
      (node (ref "J1") (pin "14") (pinfunction "14_14") (pintype "passive"))
      (node (ref "J1") (pin "35") (pinfunction "35_35") (pintype "passive"))
      (node (ref "J1") (pin "55") (pinfunction "55_55") (pintype "passive"))
      (node (ref "J1") (pin "78") (pinfunction "78_78") (pintype "passive"))
      (node (ref "J1") (pin "80") (pinfunction "80_80") (pintype "passive"))
      (node (ref "J2") (pin "04") (pinfunction "04_04") (pintype "passive"))
      (node (ref "J2") (pin "39") (pinfunction "39_39") (pintype "passive"))
      (node (ref "J3") (pin "37") (pinfunction "37_37") (pintype "passive"))
      (node (ref "J3") (pin "38") (pinfunction "38_38") (pintype "passive"))
      (node (ref "J3") (pin "39") (pinfunction "39_39") (pintype "passive"))
      (node (ref "J3") (pin "40") (pinfunction "40_40") (pintype "passive"))
      (node (ref "J4") (pin "31") (pinfunction "31_31") (pintype "passive"))
      (node (ref "J4") (pin "33") (pinfunction "33_33") (pintype "passive"))
      (node (ref "J4") (pin "35") (pinfunction "35_35") (pintype "passive"))
      (node (ref "J4") (pin "37") (pinfunction "37_37") (pintype "passive"))
      (node (ref "J4") (pin "39") (pinfunction "39_39") (pintype "passive"))
      (node (ref "J6") (pin "01") (pinfunction "01_01") (pintype "passive"))
      (node (ref "J6") (pin "13") (pinfunction "13_13") (pintype "passive"))
      (node (ref "J6") (pin "14") (pinfunction "14_14") (pintype "passive"))
      (node (ref "J6") (pin "36") (pinfunction "36_36") (pintype "passive"))
      (node (ref "J6") (pin "56") (pinfunction "56_56") (pintype "passive"))
      (node (ref "J6") (pin "78") (pinfunction "78_78") (pintype "passive"))
      (node (ref "J6") (pin "80") (pinfunction "80_80") (pintype "passive"))
    )
    (net (code "141") (name "VCCO_MC1") (class "Default")
      (node (ref "J1") (pin "36") (pinfunction "36_36") (pintype "passive"))
      (node (ref "J1") (pin "56") (pinfunction "56_56") (pintype "passive"))
      (node (ref "J3") (pin "15") (pinfunction "15_15") (pintype "passive"))
      (node (ref "J3") (pin "25") (pinfunction "25_25") (pintype "passive"))
    )
    (net (code "142") (name "VCCO_MC2") (class "Default")
      (node (ref "J4") (pin "22") (pinfunction "22_22") (pintype "passive"))
      (node (ref "J4") (pin "25") (pinfunction "25_25") (pintype "passive"))
      (node (ref "J6") (pin "35") (pinfunction "35_35") (pintype "passive"))
      (node (ref "J6") (pin "55") (pinfunction "55_55") (pintype "passive"))
    )
  )
)
